# SparkFun_MS5803-14BA_Breakout.net
KiCad netlist of a schematic drawn in EAGLE
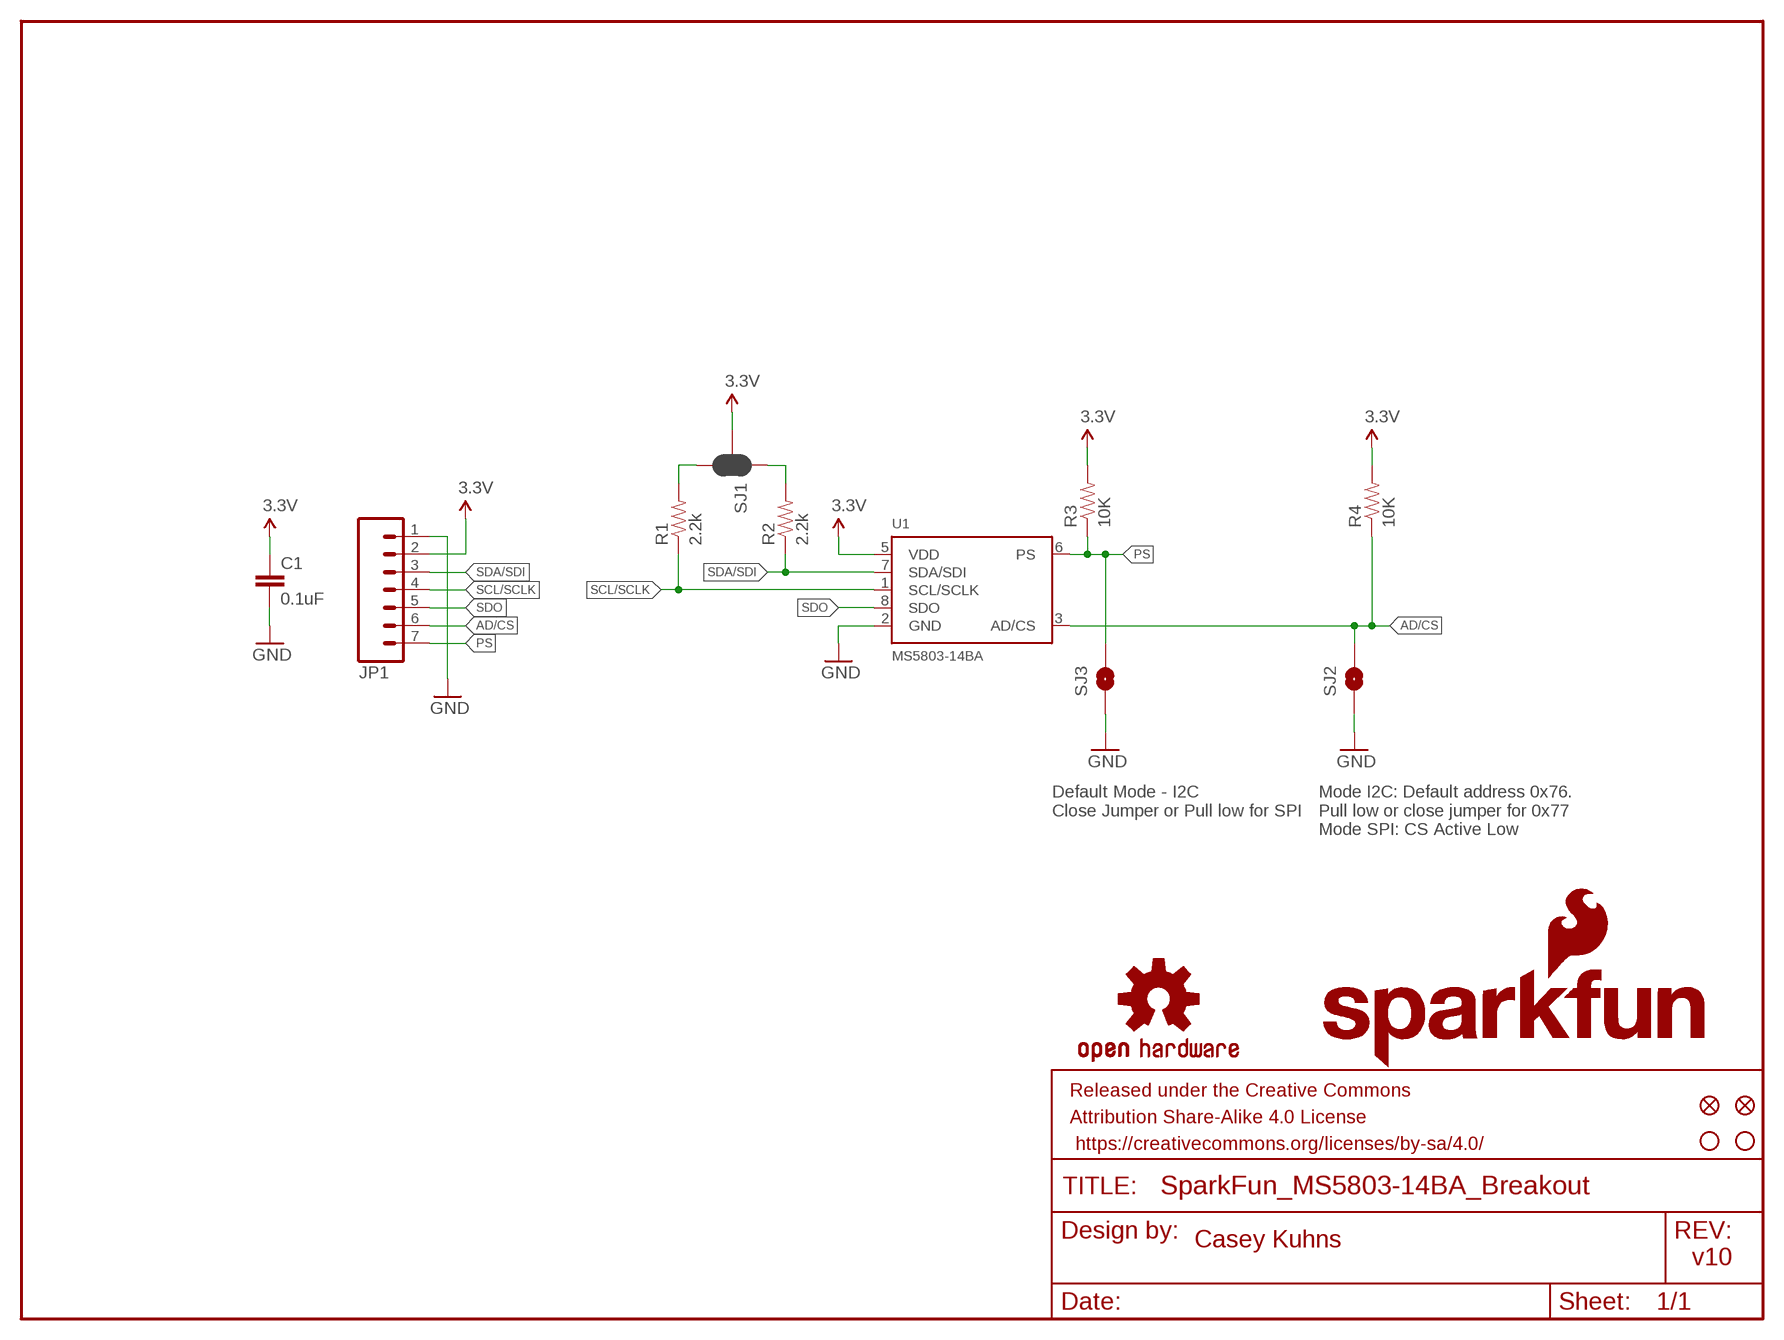
[diagram p0: schematic, sheet 1]

(export (version "E")
  (design (tool "Eeschema 10.0.6"))
  (components
    (comp (ref "C1")
      (value "0.1uF")
      (footprint "eagle-import:0603-CAP")
      (libsource (lib "eagle-import") (part "0.1UF-25V(+80/-20%)(0603)"))
    )
    (comp (ref "FID1")
      (value "FIDUCIAL1X2")
      (footprint "eagle-import:FIDUCIAL-1X2")
      (libsource (lib "eagle-import") (part "FIDUCIAL1X2"))
    )
    (comp (ref "FID2")
      (value "FIDUCIAL1X2")
      (footprint "eagle-import:FIDUCIAL-1X2")
      (libsource (lib "eagle-import") (part "FIDUCIAL1X2"))
    )
    (comp (ref "FRAME1")
      (value "FRAME-LETTER")
      (footprint "eagle-import:CREATIVE_COMMONS")
      (libsource (lib "eagle-import") (part "FRAME-LETTER"))
    )
    (comp (ref "JP1")
      (value "M07")
      (footprint "eagle-import:1X07")
      (libsource (lib "eagle-import") (part "M07"))
    )
    (comp (ref "LOGO1")
      (value "SFE_LOGO_FLAME.1_INCH")
      (footprint "eagle-import:SFE_LOGO_FLAME_.1")
      (libsource (lib "eagle-import") (part "SFE_LOGO_FLAME.1_INCH"))
    )
    (comp (ref "LOGO2")
      (value "SFE_LOGO_NAME_FLAME.1_INCH")
      (footprint "eagle-import:SFE_LOGO_NAME_FLAME_.1")
      (libsource (lib "eagle-import") (part "SFE_LOGO_NAME_FLAME.1_INCH"))
    )
    (comp (ref "LOGO3")
      (value "OSHW-LOGOS")
      (footprint "eagle-import:OSHW-LOGO-S")
      (libsource (lib "eagle-import") (part "OSHW-LOGOS"))
    )
    (comp (ref "R1")
      (value "2.2k")
      (footprint "eagle-import:0603-RES")
      (libsource (lib "eagle-import") (part "2.2KOHM1/10W1%(0603)"))
    )
    (comp (ref "R2")
      (value "2.2k")
      (footprint "eagle-import:0603-RES")
      (libsource (lib "eagle-import") (part "2.2KOHM1/10W1%(0603)"))
    )
    (comp (ref "R3")
      (value "10K")
      (footprint "eagle-import:0603-RES")
      (libsource (lib "eagle-import") (part "10KOHM1/10W1%(0603)0603"))
    )
    (comp (ref "R4")
      (value "10K")
      (footprint "eagle-import:0603-RES")
      (libsource (lib "eagle-import") (part "10KOHM1/10W1%(0603)0603"))
    )
    (comp (ref "SJ1")
      (value "JUMPER-PAD-3-NC_BY_PASTE")
      (footprint "eagle-import:PAD-JUMPER-3-NC_BY_PASTE_YES_SILK_FULL_BOX")
      (libsource (lib "eagle-import") (part "JUMPER-PAD-3-NC_BY_PASTE"))
    )
    (comp (ref "SJ2")
      (value "SOLDERJUMPERNO")
      (footprint "eagle-import:SJ_2S-NO")
      (libsource (lib "eagle-import") (part "SOLDERJUMPERNO"))
    )
    (comp (ref "SJ3")
      (value "SOLDERJUMPERNO")
      (footprint "eagle-import:SJ_2S-NO")
      (libsource (lib "eagle-import") (part "SOLDERJUMPERNO"))
    )
    (comp (ref "STANDOFF1")
      (value "STAND-OFFTIGHT")
      (footprint "eagle-import:STAND-OFF-TIGHT")
      (libsource (lib "eagle-import") (part "STAND-OFFTIGHT"))
    )
    (comp (ref "STANDOFF2")
      (value "STAND-OFFTIGHT")
      (footprint "eagle-import:STAND-OFF-TIGHT")
      (libsource (lib "eagle-import") (part "STAND-OFFTIGHT"))
    )
    (comp (ref "U1")
      (value "MS5803-14BA")
      (footprint "eagle-import:MS5803")
      (libsource (lib "eagle-import") (part "MS5803-14BA"))
    )
  )
  (nets
    (net (code "1") (name "3.3V") (class "Default")
      (node (ref "C1") (pin "1") (pinfunction "1_1") (pintype "passive"))
      (node (ref "JP1") (pin "2") (pinfunction "2_2") (pintype "passive"))
      (node (ref "R3") (pin "2") (pinfunction "2_2") (pintype "passive"))
      (node (ref "R4") (pin "2") (pinfunction "2_2") (pintype "passive"))
      (node (ref "SJ1") (pin "2") (pinfunction "2_2") (pintype "passive"))
      (node (ref "U1") (pin "5") (pinfunction "VDD_5") (pintype "bidirectional"))
    )
    (net (code "2") (name "AD{slash}CS") (class "Default")
      (node (ref "JP1") (pin "6") (pinfunction "6_6") (pintype "passive"))
      (node (ref "R4") (pin "1") (pinfunction "1_1") (pintype "passive"))
      (node (ref "SJ2") (pin "2") (pinfunction "2_2") (pintype "passive"))
      (node (ref "U1") (pin "3") (pinfunction "AD/CS_3") (pintype "bidirectional"))
    )
    (net (code "3") (name "GND") (class "Default")
      (node (ref "C1") (pin "2") (pinfunction "2_2") (pintype "passive"))
      (node (ref "JP1") (pin "1") (pinfunction "1_1") (pintype "passive"))
      (node (ref "SJ2") (pin "1") (pinfunction "1_1") (pintype "passive"))
      (node (ref "SJ3") (pin "1") (pinfunction "1_1") (pintype "passive"))
      (node (ref "U1") (pin "2") (pinfunction "GND_2") (pintype "bidirectional"))
    )
    (net (code "4") (name "Net-(R1-Pad2)") (class "Default")
      (node (ref "R1") (pin "2") (pinfunction "2_2") (pintype "passive"))
      (node (ref "SJ1") (pin "3") (pinfunction "3_3") (pintype "passive"))
    )
    (net (code "5") (name "Net-(R2-Pad2)") (class "Default")
      (node (ref "R2") (pin "2") (pinfunction "2_2") (pintype "passive"))
      (node (ref "SJ1") (pin "1") (pinfunction "1_1") (pintype "passive"))
    )
    (net (code "6") (name "PS") (class "Default")
      (node (ref "JP1") (pin "7") (pinfunction "7_7") (pintype "passive"))
      (node (ref "R3") (pin "1") (pinfunction "1_1") (pintype "passive"))
      (node (ref "SJ3") (pin "2") (pinfunction "2_2") (pintype "passive"))
      (node (ref "U1") (pin "6") (pinfunction "PS_6") (pintype "bidirectional"))
    )
    (net (code "7") (name "SCL{slash}SCLK") (class "Default")
      (node (ref "JP1") (pin "4") (pinfunction "4_4") (pintype "passive"))
      (node (ref "R1") (pin "1") (pinfunction "1_1") (pintype "passive"))
      (node (ref "U1") (pin "1") (pinfunction "SCL/SCLK_1") (pintype "bidirectional"))
    )
    (net (code "8") (name "SDA{slash}SDI") (class "Default")
      (node (ref "JP1") (pin "3") (pinfunction "3_3") (pintype "passive"))
      (node (ref "R2") (pin "1") (pinfunction "1_1") (pintype "passive"))
      (node (ref "U1") (pin "7") (pinfunction "SDA/SDI_7") (pintype "bidirectional"))
    )
    (net (code "9") (name "SDO") (class "Default")
      (node (ref "JP1") (pin "5") (pinfunction "5_5") (pintype "passive"))
      (node (ref "U1") (pin "8") (pinfunction "SDO_8") (pintype "bidirectional"))
    )
  )
)
